# Bus.net
KiCad netlist of a schematic drawn in EAGLE
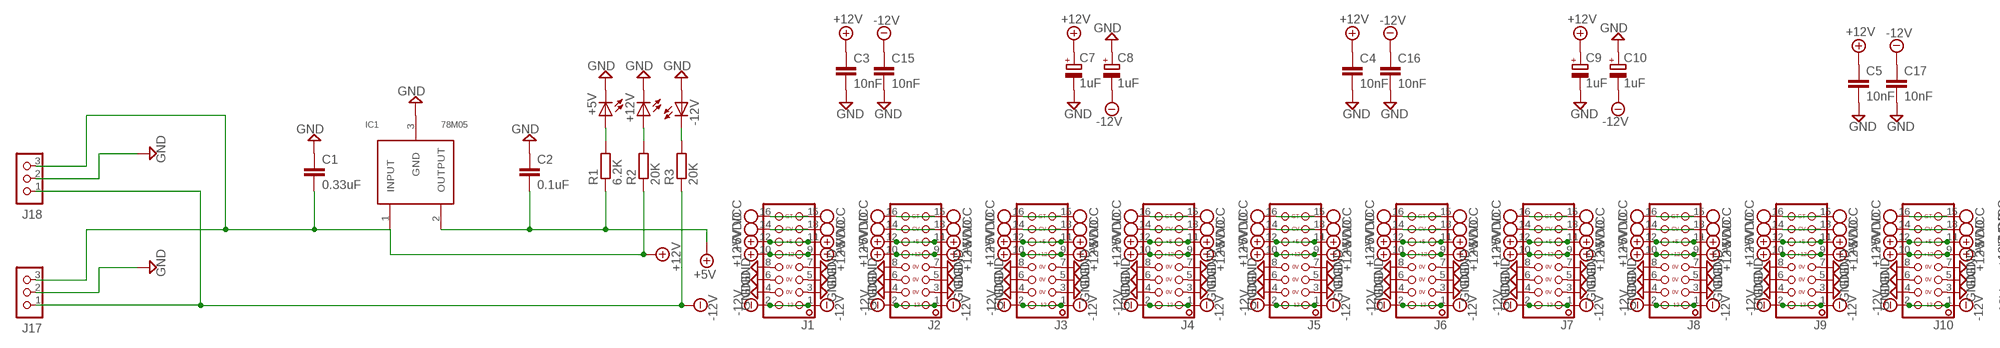
[diagram p0: schematic, sheet 1, part 1 of 2]
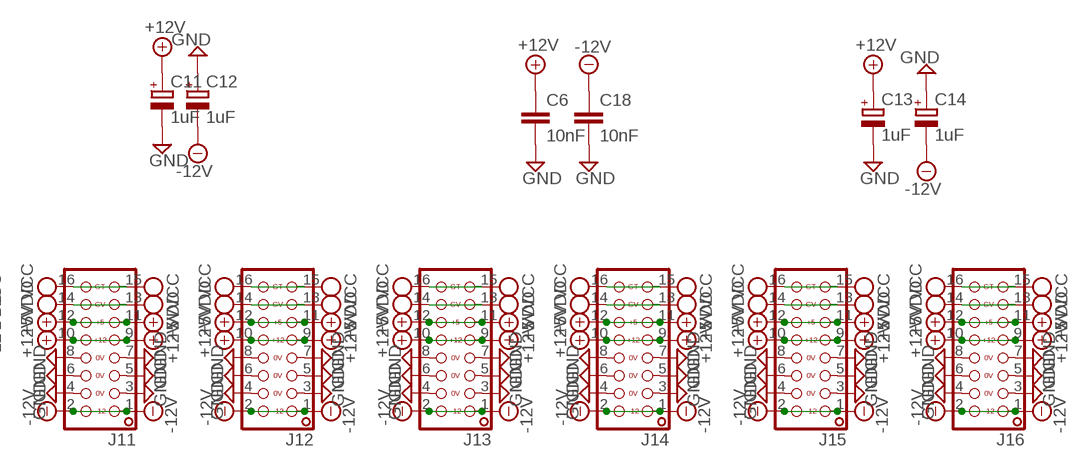
[diagram p1: schematic, sheet 1, part 2 of 2]

(export (version "E")
  (design (tool "Eeschema 10.0.6"))
  (components
    (comp (ref "+5V")
      (value "LED3MM")
      (footprint "eagle-import:LED3MM")
      (libsource (lib "eagle-import") (part "LED3MM"))
    )
    (comp (ref "+12V")
      (value "LED3MM")
      (footprint "eagle-import:LED3MM")
      (libsource (lib "eagle-import") (part "LED3MM"))
    )
    (comp (ref "-12V")
      (value "LED3MM")
      (footprint "eagle-import:LED3MM")
      (libsource (lib "eagle-import") (part "LED3MM"))
    )
    (comp (ref "C1")
      (value "0.33uF")
      (footprint "eagle-import:C1206")
      (libsource (lib "eagle-import") (part "C-EUC1206"))
    )
    (comp (ref "C2")
      (value "0.1uF")
      (footprint "eagle-import:C1206")
      (libsource (lib "eagle-import") (part "C-EUC1206"))
    )
    (comp (ref "C3")
      (value "10nF")
      (footprint "eagle-import:C1206")
      (libsource (lib "eagle-import") (part "C-EUC1206"))
    )
    (comp (ref "C4")
      (value "10nF")
      (footprint "eagle-import:C1206")
      (libsource (lib "eagle-import") (part "C-EUC1206"))
    )
    (comp (ref "C5")
      (value "10nF")
      (footprint "eagle-import:C1206")
      (libsource (lib "eagle-import") (part "C-EUC1206"))
    )
    (comp (ref "C6")
      (value "10nF")
      (footprint "eagle-import:C1206")
      (libsource (lib "eagle-import") (part "C-EUC1206"))
    )
    (comp (ref "C7")
      (value "1uF")
      (footprint "eagle-import:PANASONIC_A")
      (libsource (lib "eagle-import") (part "CPOL-EUA"))
    )
    (comp (ref "C8")
      (value "1uF")
      (footprint "eagle-import:PANASONIC_A")
      (libsource (lib "eagle-import") (part "CPOL-EUA"))
    )
    (comp (ref "C9")
      (value "1uF")
      (footprint "eagle-import:PANASONIC_A")
      (libsource (lib "eagle-import") (part "CPOL-EUA"))
    )
    (comp (ref "C10")
      (value "1uF")
      (footprint "eagle-import:PANASONIC_A")
      (libsource (lib "eagle-import") (part "CPOL-EUA"))
    )
    (comp (ref "C11")
      (value "1uF")
      (footprint "eagle-import:PANASONIC_A")
      (libsource (lib "eagle-import") (part "CPOL-EUA"))
    )
    (comp (ref "C12")
      (value "1uF")
      (footprint "eagle-import:PANASONIC_A")
      (libsource (lib "eagle-import") (part "CPOL-EUA"))
    )
    (comp (ref "C13")
      (value "1uF")
      (footprint "eagle-import:PANASONIC_A")
      (libsource (lib "eagle-import") (part "CPOL-EUA"))
    )
    (comp (ref "C14")
      (value "1uF")
      (footprint "eagle-import:PANASONIC_A")
      (libsource (lib "eagle-import") (part "CPOL-EUA"))
    )
    (comp (ref "C15")
      (value "10nF")
      (footprint "eagle-import:C1206")
      (libsource (lib "eagle-import") (part "C-EUC1206"))
    )
    (comp (ref "C16")
      (value "10nF")
      (footprint "eagle-import:C1206")
      (libsource (lib "eagle-import") (part "C-EUC1206"))
    )
    (comp (ref "C17")
      (value "10nF")
      (footprint "eagle-import:C1206")
      (libsource (lib "eagle-import") (part "C-EUC1206"))
    )
    (comp (ref "C18")
      (value "10nF")
      (footprint "eagle-import:C1206")
      (libsource (lib "eagle-import") (part "C-EUC1206"))
    )
    (comp (ref "IC1")
      (value "78M05")
      (footprint "eagle-import:TO252")
      (libsource (lib "eagle-import") (part "78MXX"))
    )
    (comp (ref "J1")
      (value "EUROPWR_2X08-SHROUD")
      (footprint "eagle-import:2X08_EUROPWR_SHROUD")
      (libsource (lib "eagle-import") (part "EUROPWR_2X08-SHROUD"))
    )
    (comp (ref "J2")
      (value "EUROPWR_2X08-SHROUD")
      (footprint "eagle-import:2X08_EUROPWR_SHROUD")
      (libsource (lib "eagle-import") (part "EUROPWR_2X08-SHROUD"))
    )
    (comp (ref "J3")
      (value "EUROPWR_2X08-SHROUD")
      (footprint "eagle-import:2X08_EUROPWR_SHROUD")
      (libsource (lib "eagle-import") (part "EUROPWR_2X08-SHROUD"))
    )
    (comp (ref "J4")
      (value "EUROPWR_2X08-SHROUD")
      (footprint "eagle-import:2X08_EUROPWR_SHROUD")
      (libsource (lib "eagle-import") (part "EUROPWR_2X08-SHROUD"))
    )
    (comp (ref "J5")
      (value "EUROPWR_2X08-SHROUD")
      (footprint "eagle-import:2X08_EUROPWR_SHROUD")
      (libsource (lib "eagle-import") (part "EUROPWR_2X08-SHROUD"))
    )
    (comp (ref "J6")
      (value "EUROPWR_2X08-SHROUD")
      (footprint "eagle-import:2X08_EUROPWR_SHROUD")
      (libsource (lib "eagle-import") (part "EUROPWR_2X08-SHROUD"))
    )
    (comp (ref "J7")
      (value "EUROPWR_2X08-SHROUD")
      (footprint "eagle-import:2X08_EUROPWR_SHROUD")
      (libsource (lib "eagle-import") (part "EUROPWR_2X08-SHROUD"))
    )
    (comp (ref "J8")
      (value "EUROPWR_2X08-SHROUD")
      (footprint "eagle-import:2X08_EUROPWR_SHROUD")
      (libsource (lib "eagle-import") (part "EUROPWR_2X08-SHROUD"))
    )
    (comp (ref "J9")
      (value "EUROPWR_2X08-SHROUD")
      (footprint "eagle-import:2X08_EUROPWR_SHROUD")
      (libsource (lib "eagle-import") (part "EUROPWR_2X08-SHROUD"))
    )
    (comp (ref "J10")
      (value "EUROPWR_2X08-SHROUD")
      (footprint "eagle-import:2X08_EUROPWR_SHROUD")
      (libsource (lib "eagle-import") (part "EUROPWR_2X08-SHROUD"))
    )
    (comp (ref "J11")
      (value "EUROPWR_2X08-SHROUD")
      (footprint "eagle-import:2X08_EUROPWR_SHROUD")
      (libsource (lib "eagle-import") (part "EUROPWR_2X08-SHROUD"))
    )
    (comp (ref "J12")
      (value "EUROPWR_2X08-SHROUD")
      (footprint "eagle-import:2X08_EUROPWR_SHROUD")
      (libsource (lib "eagle-import") (part "EUROPWR_2X08-SHROUD"))
    )
    (comp (ref "J13")
      (value "EUROPWR_2X08-SHROUD")
      (footprint "eagle-import:2X08_EUROPWR_SHROUD")
      (libsource (lib "eagle-import") (part "EUROPWR_2X08-SHROUD"))
    )
    (comp (ref "J14")
      (value "EUROPWR_2X08-SHROUD")
      (footprint "eagle-import:2X08_EUROPWR_SHROUD")
      (libsource (lib "eagle-import") (part "EUROPWR_2X08-SHROUD"))
    )
    (comp (ref "J15")
      (value "EUROPWR_2X08-SHROUD")
      (footprint "eagle-import:2X08_EUROPWR_SHROUD")
      (libsource (lib "eagle-import") (part "EUROPWR_2X08-SHROUD"))
    )
    (comp (ref "J16")
      (value "EUROPWR_2X08-SHROUD")
      (footprint "eagle-import:2X08_EUROPWR_SHROUD")
      (libsource (lib "eagle-import") (part "EUROPWR_2X08-SHROUD"))
    )
    (comp (ref "J17")
      (value "CON_TERMINAL_BLOCK_03-5MM")
      (footprint "eagle-import:TERMINAL_BLOCK_3P_5")
      (libsource (lib "eagle-import") (part "CON_TERMINAL_BLOCK_03-5MM"))
    )
    (comp (ref "J18")
      (value "CON_TERMINAL_BLOCK_03-5MM")
      (footprint "eagle-import:TERMINAL_BLOCK_3P_5")
      (libsource (lib "eagle-import") (part "CON_TERMINAL_BLOCK_03-5MM"))
    )
    (comp (ref "R1")
      (value "6.2K")
      (footprint "eagle-import:R1206")
      (libsource (lib "eagle-import") (part "R-EU_R1206"))
    )
    (comp (ref "R2")
      (value "20K")
      (footprint "eagle-import:R1206")
      (libsource (lib "eagle-import") (part "R-EU_R1206"))
    )
    (comp (ref "R3")
      (value "20K")
      (footprint "eagle-import:R1206")
      (libsource (lib "eagle-import") (part "R-EU_R1206"))
    )
  )
  (nets
    (net (code "1") (name "+5V") (class "Default")
      (node (ref "C2") (pin "2") (pinfunction "2_2") (pintype "passive"))
      (node (ref "IC1") (pin "2") (pinfunction "OUTPUT_2") (pintype "bidirectional"))
      (node (ref "J1") (pin "11") (pinfunction "11_11") (pintype "passive"))
      (node (ref "J1") (pin "12") (pinfunction "12_12") (pintype "passive"))
      (node (ref "J10") (pin "11") (pinfunction "11_11") (pintype "passive"))
      (node (ref "J10") (pin "12") (pinfunction "12_12") (pintype "passive"))
      (node (ref "J11") (pin "11") (pinfunction "11_11") (pintype "passive"))
      (node (ref "J11") (pin "12") (pinfunction "12_12") (pintype "passive"))
      (node (ref "J12") (pin "11") (pinfunction "11_11") (pintype "passive"))
      (node (ref "J12") (pin "12") (pinfunction "12_12") (pintype "passive"))
      (node (ref "J13") (pin "11") (pinfunction "11_11") (pintype "passive"))
      (node (ref "J13") (pin "12") (pinfunction "12_12") (pintype "passive"))
      (node (ref "J14") (pin "11") (pinfunction "11_11") (pintype "passive"))
      (node (ref "J14") (pin "12") (pinfunction "12_12") (pintype "passive"))
      (node (ref "J15") (pin "11") (pinfunction "11_11") (pintype "passive"))
      (node (ref "J15") (pin "12") (pinfunction "12_12") (pintype "passive"))
      (node (ref "J16") (pin "11") (pinfunction "11_11") (pintype "passive"))
      (node (ref "J16") (pin "12") (pinfunction "12_12") (pintype "passive"))
      (node (ref "J2") (pin "11") (pinfunction "11_11") (pintype "passive"))
      (node (ref "J2") (pin "12") (pinfunction "12_12") (pintype "passive"))
      (node (ref "J3") (pin "11") (pinfunction "11_11") (pintype "passive"))
      (node (ref "J3") (pin "12") (pinfunction "12_12") (pintype "passive"))
      (node (ref "J4") (pin "11") (pinfunction "11_11") (pintype "passive"))
      (node (ref "J4") (pin "12") (pinfunction "12_12") (pintype "passive"))
      (node (ref "J5") (pin "11") (pinfunction "11_11") (pintype "passive"))
      (node (ref "J5") (pin "12") (pinfunction "12_12") (pintype "passive"))
      (node (ref "J6") (pin "11") (pinfunction "11_11") (pintype "passive"))
      (node (ref "J6") (pin "12") (pinfunction "12_12") (pintype "passive"))
      (node (ref "J7") (pin "11") (pinfunction "11_11") (pintype "passive"))
      (node (ref "J7") (pin "12") (pinfunction "12_12") (pintype "passive"))
      (node (ref "J8") (pin "11") (pinfunction "11_11") (pintype "passive"))
      (node (ref "J8") (pin "12") (pinfunction "12_12") (pintype "passive"))
      (node (ref "J9") (pin "11") (pinfunction "11_11") (pintype "passive"))
      (node (ref "J9") (pin "12") (pinfunction "12_12") (pintype "passive"))
      (node (ref "R1") (pin "1") (pinfunction "1_1") (pintype "passive"))
    )
    (net (code "2") (name "+12V") (class "Default")
      (node (ref "C1") (pin "2") (pinfunction "2_2") (pintype "passive"))
      (node (ref "C11") (pin "+") (pinfunction "+_+") (pintype "passive"))
      (node (ref "C13") (pin "+") (pinfunction "+_+") (pintype "passive"))
      (node (ref "C3") (pin "1") (pinfunction "1_1") (pintype "passive"))
      (node (ref "C4") (pin "1") (pinfunction "1_1") (pintype "passive"))
      (node (ref "C5") (pin "1") (pinfunction "1_1") (pintype "passive"))
      (node (ref "C6") (pin "1") (pinfunction "1_1") (pintype "passive"))
      (node (ref "C7") (pin "+") (pinfunction "+_+") (pintype "passive"))
      (node (ref "C9") (pin "+") (pinfunction "+_+") (pintype "passive"))
      (node (ref "IC1") (pin "1") (pinfunction "INPUT_1") (pintype "bidirectional"))
      (node (ref "J1") (pin "10") (pinfunction "10_10") (pintype "passive"))
      (node (ref "J1") (pin "9") (pinfunction "9_9") (pintype "passive"))
      (node (ref "J10") (pin "10") (pinfunction "10_10") (pintype "passive"))
      (node (ref "J10") (pin "9") (pinfunction "9_9") (pintype "passive"))
      (node (ref "J11") (pin "10") (pinfunction "10_10") (pintype "passive"))
      (node (ref "J11") (pin "9") (pinfunction "9_9") (pintype "passive"))
      (node (ref "J12") (pin "10") (pinfunction "10_10") (pintype "passive"))
      (node (ref "J12") (pin "9") (pinfunction "9_9") (pintype "passive"))
      (node (ref "J13") (pin "10") (pinfunction "10_10") (pintype "passive"))
      (node (ref "J13") (pin "9") (pinfunction "9_9") (pintype "passive"))
      (node (ref "J14") (pin "10") (pinfunction "10_10") (pintype "passive"))
      (node (ref "J14") (pin "9") (pinfunction "9_9") (pintype "passive"))
      (node (ref "J15") (pin "10") (pinfunction "10_10") (pintype "passive"))
      (node (ref "J15") (pin "9") (pinfunction "9_9") (pintype "passive"))
      (node (ref "J16") (pin "10") (pinfunction "10_10") (pintype "passive"))
      (node (ref "J16") (pin "9") (pinfunction "9_9") (pintype "passive"))
      (node (ref "J17") (pin "3") (pinfunction "3_3") (pintype "bidirectional"))
      (node (ref "J18") (pin "3") (pinfunction "3_3") (pintype "bidirectional"))
      (node (ref "J2") (pin "10") (pinfunction "10_10") (pintype "passive"))
      (node (ref "J2") (pin "9") (pinfunction "9_9") (pintype "passive"))
      (node (ref "J3") (pin "10") (pinfunction "10_10") (pintype "passive"))
      (node (ref "J3") (pin "9") (pinfunction "9_9") (pintype "passive"))
      (node (ref "J4") (pin "10") (pinfunction "10_10") (pintype "passive"))
      (node (ref "J4") (pin "9") (pinfunction "9_9") (pintype "passive"))
      (node (ref "J5") (pin "10") (pinfunction "10_10") (pintype "passive"))
      (node (ref "J5") (pin "9") (pinfunction "9_9") (pintype "passive"))
      (node (ref "J6") (pin "10") (pinfunction "10_10") (pintype "passive"))
      (node (ref "J6") (pin "9") (pinfunction "9_9") (pintype "passive"))
      (node (ref "J7") (pin "10") (pinfunction "10_10") (pintype "passive"))
      (node (ref "J7") (pin "9") (pinfunction "9_9") (pintype "passive"))
      (node (ref "J8") (pin "10") (pinfunction "10_10") (pintype "passive"))
      (node (ref "J8") (pin "9") (pinfunction "9_9") (pintype "passive"))
      (node (ref "J9") (pin "10") (pinfunction "10_10") (pintype "passive"))
      (node (ref "J9") (pin "9") (pinfunction "9_9") (pintype "passive"))
      (node (ref "R2") (pin "1") (pinfunction "1_1") (pintype "passive"))
    )
    (net (code "3") (name "-12V") (class "Default")
      (node (ref "C10") (pin "-") (pinfunction "-_-") (pintype "passive"))
      (node (ref "C12") (pin "-") (pinfunction "-_-") (pintype "passive"))
      (node (ref "C14") (pin "-") (pinfunction "-_-") (pintype "passive"))
      (node (ref "C15") (pin "1") (pinfunction "1_1") (pintype "passive"))
      (node (ref "C16") (pin "1") (pinfunction "1_1") (pintype "passive"))
      (node (ref "C17") (pin "1") (pinfunction "1_1") (pintype "passive"))
      (node (ref "C18") (pin "1") (pinfunction "1_1") (pintype "passive"))
      (node (ref "C8") (pin "-") (pinfunction "-_-") (pintype "passive"))
      (node (ref "J1") (pin "1") (pinfunction "1_1") (pintype "passive"))
      (node (ref "J1") (pin "2") (pinfunction "2_2") (pintype "passive"))
      (node (ref "J10") (pin "1") (pinfunction "1_1") (pintype "passive"))
      (node (ref "J10") (pin "2") (pinfunction "2_2") (pintype "passive"))
      (node (ref "J11") (pin "1") (pinfunction "1_1") (pintype "passive"))
      (node (ref "J11") (pin "2") (pinfunction "2_2") (pintype "passive"))
      (node (ref "J12") (pin "1") (pinfunction "1_1") (pintype "passive"))
      (node (ref "J12") (pin "2") (pinfunction "2_2") (pintype "passive"))
      (node (ref "J13") (pin "1") (pinfunction "1_1") (pintype "passive"))
      (node (ref "J13") (pin "2") (pinfunction "2_2") (pintype "passive"))
      (node (ref "J14") (pin "1") (pinfunction "1_1") (pintype "passive"))
      (node (ref "J14") (pin "2") (pinfunction "2_2") (pintype "passive"))
      (node (ref "J15") (pin "1") (pinfunction "1_1") (pintype "passive"))
      (node (ref "J15") (pin "2") (pinfunction "2_2") (pintype "passive"))
      (node (ref "J16") (pin "1") (pinfunction "1_1") (pintype "passive"))
      (node (ref "J16") (pin "2") (pinfunction "2_2") (pintype "passive"))
      (node (ref "J17") (pin "1") (pinfunction "1_1") (pintype "bidirectional"))
      (node (ref "J18") (pin "1") (pinfunction "1_1") (pintype "bidirectional"))
      (node (ref "J2") (pin "1") (pinfunction "1_1") (pintype "passive"))
      (node (ref "J2") (pin "2") (pinfunction "2_2") (pintype "passive"))
      (node (ref "J3") (pin "1") (pinfunction "1_1") (pintype "passive"))
      (node (ref "J3") (pin "2") (pinfunction "2_2") (pintype "passive"))
      (node (ref "J4") (pin "1") (pinfunction "1_1") (pintype "passive"))
      (node (ref "J4") (pin "2") (pinfunction "2_2") (pintype "passive"))
      (node (ref "J5") (pin "1") (pinfunction "1_1") (pintype "passive"))
      (node (ref "J5") (pin "2") (pinfunction "2_2") (pintype "passive"))
      (node (ref "J6") (pin "1") (pinfunction "1_1") (pintype "passive"))
      (node (ref "J6") (pin "2") (pinfunction "2_2") (pintype "passive"))
      (node (ref "J7") (pin "1") (pinfunction "1_1") (pintype "passive"))
      (node (ref "J7") (pin "2") (pinfunction "2_2") (pintype "passive"))
      (node (ref "J8") (pin "1") (pinfunction "1_1") (pintype "passive"))
      (node (ref "J8") (pin "2") (pinfunction "2_2") (pintype "passive"))
      (node (ref "J9") (pin "1") (pinfunction "1_1") (pintype "passive"))
      (node (ref "J9") (pin "2") (pinfunction "2_2") (pintype "passive"))
      (node (ref "R3") (pin "1") (pinfunction "1_1") (pintype "passive"))
    )
    (net (code "4") (name "GND") (class "Default")
      (node (ref "+12V") (pin "K") (pinfunction "C_K") (pintype "passive"))
      (node (ref "+5V") (pin "K") (pinfunction "C_K") (pintype "passive"))
      (node (ref "-12V") (pin "A") (pinfunction "A_A") (pintype "passive"))
      (node (ref "C1") (pin "1") (pinfunction "1_1") (pintype "passive"))
      (node (ref "C10") (pin "+") (pinfunction "+_+") (pintype "passive"))
      (node (ref "C11") (pin "-") (pinfunction "-_-") (pintype "passive"))
      (node (ref "C12") (pin "+") (pinfunction "+_+") (pintype "passive"))
      (node (ref "C13") (pin "-") (pinfunction "-_-") (pintype "passive"))
      (node (ref "C14") (pin "+") (pinfunction "+_+") (pintype "passive"))
      (node (ref "C15") (pin "2") (pinfunction "2_2") (pintype "passive"))
      (node (ref "C16") (pin "2") (pinfunction "2_2") (pintype "passive"))
      (node (ref "C17") (pin "2") (pinfunction "2_2") (pintype "passive"))
      (node (ref "C18") (pin "2") (pinfunction "2_2") (pintype "passive"))
      (node (ref "C2") (pin "1") (pinfunction "1_1") (pintype "passive"))
      (node (ref "C3") (pin "2") (pinfunction "2_2") (pintype "passive"))
      (node (ref "C4") (pin "2") (pinfunction "2_2") (pintype "passive"))
      (node (ref "C5") (pin "2") (pinfunction "2_2") (pintype "passive"))
      (node (ref "C6") (pin "2") (pinfunction "2_2") (pintype "passive"))
      (node (ref "C7") (pin "-") (pinfunction "-_-") (pintype "passive"))
      (node (ref "C8") (pin "+") (pinfunction "+_+") (pintype "passive"))
      (node (ref "C9") (pin "-") (pinfunction "-_-") (pintype "passive"))
      (node (ref "IC1") (pin "3") (pinfunction "GND_3") (pintype "bidirectional"))
      (node (ref "J1") (pin "3") (pinfunction "3_3") (pintype "passive"))
      (node (ref "J1") (pin "4") (pinfunction "4_4") (pintype "passive"))
      (node (ref "J1") (pin "5") (pinfunction "5_5") (pintype "passive"))
      (node (ref "J1") (pin "6") (pinfunction "6_6") (pintype "passive"))
      (node (ref "J1") (pin "7") (pinfunction "7_7") (pintype "passive"))
      (node (ref "J1") (pin "8") (pinfunction "8_8") (pintype "passive"))
      (node (ref "J10") (pin "3") (pinfunction "3_3") (pintype "passive"))
      (node (ref "J10") (pin "4") (pinfunction "4_4") (pintype "passive"))
      (node (ref "J10") (pin "5") (pinfunction "5_5") (pintype "passive"))
      (node (ref "J10") (pin "6") (pinfunction "6_6") (pintype "passive"))
      (node (ref "J10") (pin "7") (pinfunction "7_7") (pintype "passive"))
      (node (ref "J10") (pin "8") (pinfunction "8_8") (pintype "passive"))
      (node (ref "J11") (pin "3") (pinfunction "3_3") (pintype "passive"))
      (node (ref "J11") (pin "4") (pinfunction "4_4") (pintype "passive"))
      (node (ref "J11") (pin "5") (pinfunction "5_5") (pintype "passive"))
      (node (ref "J11") (pin "6") (pinfunction "6_6") (pintype "passive"))
      (node (ref "J11") (pin "7") (pinfunction "7_7") (pintype "passive"))
      (node (ref "J11") (pin "8") (pinfunction "8_8") (pintype "passive"))
      (node (ref "J12") (pin "3") (pinfunction "3_3") (pintype "passive"))
      (node (ref "J12") (pin "4") (pinfunction "4_4") (pintype "passive"))
      (node (ref "J12") (pin "5") (pinfunction "5_5") (pintype "passive"))
      (node (ref "J12") (pin "6") (pinfunction "6_6") (pintype "passive"))
      (node (ref "J12") (pin "7") (pinfunction "7_7") (pintype "passive"))
      (node (ref "J12") (pin "8") (pinfunction "8_8") (pintype "passive"))
      (node (ref "J13") (pin "3") (pinfunction "3_3") (pintype "passive"))
      (node (ref "J13") (pin "4") (pinfunction "4_4") (pintype "passive"))
      (node (ref "J13") (pin "5") (pinfunction "5_5") (pintype "passive"))
      (node (ref "J13") (pin "6") (pinfunction "6_6") (pintype "passive"))
      (node (ref "J13") (pin "7") (pinfunction "7_7") (pintype "passive"))
      (node (ref "J13") (pin "8") (pinfunction "8_8") (pintype "passive"))
      (node (ref "J14") (pin "3") (pinfunction "3_3") (pintype "passive"))
      (node (ref "J14") (pin "4") (pinfunction "4_4") (pintype "passive"))
      (node (ref "J14") (pin "5") (pinfunction "5_5") (pintype "passive"))
      (node (ref "J14") (pin "6") (pinfunction "6_6") (pintype "passive"))
      (node (ref "J14") (pin "7") (pinfunction "7_7") (pintype "passive"))
      (node (ref "J14") (pin "8") (pinfunction "8_8") (pintype "passive"))
      (node (ref "J15") (pin "3") (pinfunction "3_3") (pintype "passive"))
      (node (ref "J15") (pin "4") (pinfunction "4_4") (pintype "passive"))
      (node (ref "J15") (pin "5") (pinfunction "5_5") (pintype "passive"))
      (node (ref "J15") (pin "6") (pinfunction "6_6") (pintype "passive"))
      (node (ref "J15") (pin "7") (pinfunction "7_7") (pintype "passive"))
      (node (ref "J15") (pin "8") (pinfunction "8_8") (pintype "passive"))
      (node (ref "J16") (pin "3") (pinfunction "3_3") (pintype "passive"))
      (node (ref "J16") (pin "4") (pinfunction "4_4") (pintype "passive"))
      (node (ref "J16") (pin "5") (pinfunction "5_5") (pintype "passive"))
      (node (ref "J16") (pin "6") (pinfunction "6_6") (pintype "passive"))
      (node (ref "J16") (pin "7") (pinfunction "7_7") (pintype "passive"))
      (node (ref "J16") (pin "8") (pinfunction "8_8") (pintype "passive"))
      (node (ref "J17") (pin "2") (pinfunction "2_2") (pintype "bidirectional"))
      (node (ref "J18") (pin "2") (pinfunction "2_2") (pintype "bidirectional"))
      (node (ref "J2") (pin "3") (pinfunction "3_3") (pintype "passive"))
      (node (ref "J2") (pin "4") (pinfunction "4_4") (pintype "passive"))
      (node (ref "J2") (pin "5") (pinfunction "5_5") (pintype "passive"))
      (node (ref "J2") (pin "6") (pinfunction "6_6") (pintype "passive"))
      (node (ref "J2") (pin "7") (pinfunction "7_7") (pintype "passive"))
      (node (ref "J2") (pin "8") (pinfunction "8_8") (pintype "passive"))
      (node (ref "J3") (pin "3") (pinfunction "3_3") (pintype "passive"))
      (node (ref "J3") (pin "4") (pinfunction "4_4") (pintype "passive"))
      (node (ref "J3") (pin "5") (pinfunction "5_5") (pintype "passive"))
      (node (ref "J3") (pin "6") (pinfunction "6_6") (pintype "passive"))
      (node (ref "J3") (pin "7") (pinfunction "7_7") (pintype "passive"))
      (node (ref "J3") (pin "8") (pinfunction "8_8") (pintype "passive"))
      (node (ref "J4") (pin "3") (pinfunction "3_3") (pintype "passive"))
      (node (ref "J4") (pin "4") (pinfunction "4_4") (pintype "passive"))
      (node (ref "J4") (pin "5") (pinfunction "5_5") (pintype "passive"))
      (node (ref "J4") (pin "6") (pinfunction "6_6") (pintype "passive"))
      (node (ref "J4") (pin "7") (pinfunction "7_7") (pintype "passive"))
      (node (ref "J4") (pin "8") (pinfunction "8_8") (pintype "passive"))
      (node (ref "J5") (pin "3") (pinfunction "3_3") (pintype "passive"))
      (node (ref "J5") (pin "4") (pinfunction "4_4") (pintype "passive"))
      (node (ref "J5") (pin "5") (pinfunction "5_5") (pintype "passive"))
      (node (ref "J5") (pin "6") (pinfunction "6_6") (pintype "passive"))
      (node (ref "J5") (pin "7") (pinfunction "7_7") (pintype "passive"))
      (node (ref "J5") (pin "8") (pinfunction "8_8") (pintype "passive"))
      (node (ref "J6") (pin "3") (pinfunction "3_3") (pintype "passive"))
      (node (ref "J6") (pin "4") (pinfunction "4_4") (pintype "passive"))
      (node (ref "J6") (pin "5") (pinfunction "5_5") (pintype "passive"))
      (node (ref "J6") (pin "6") (pinfunction "6_6") (pintype "passive"))
      (node (ref "J6") (pin "7") (pinfunction "7_7") (pintype "passive"))
      (node (ref "J6") (pin "8") (pinfunction "8_8") (pintype "passive"))
      (node (ref "J7") (pin "3") (pinfunction "3_3") (pintype "passive"))
      (node (ref "J7") (pin "4") (pinfunction "4_4") (pintype "passive"))
      (node (ref "J7") (pin "5") (pinfunction "5_5") (pintype "passive"))
      (node (ref "J7") (pin "6") (pinfunction "6_6") (pintype "passive"))
      (node (ref "J7") (pin "7") (pinfunction "7_7") (pintype "passive"))
      (node (ref "J7") (pin "8") (pinfunction "8_8") (pintype "passive"))
      (node (ref "J8") (pin "3") (pinfunction "3_3") (pintype "passive"))
      (node (ref "J8") (pin "4") (pinfunction "4_4") (pintype "passive"))
      (node (ref "J8") (pin "5") (pinfunction "5_5") (pintype "passive"))
      (node (ref "J8") (pin "6") (pinfunction "6_6") (pintype "passive"))
      (node (ref "J8") (pin "7") (pinfunction "7_7") (pintype "passive"))
      (node (ref "J8") (pin "8") (pinfunction "8_8") (pintype "passive"))
      (node (ref "J9") (pin "3") (pinfunction "3_3") (pintype "passive"))
      (node (ref "J9") (pin "4") (pinfunction "4_4") (pintype "passive"))
      (node (ref "J9") (pin "5") (pinfunction "5_5") (pintype "passive"))
      (node (ref "J9") (pin "6") (pinfunction "6_6") (pintype "passive"))
      (node (ref "J9") (pin "7") (pinfunction "7_7") (pintype "passive"))
      (node (ref "J9") (pin "8") (pinfunction "8_8") (pintype "passive"))
    )
    (net (code "5") (name "Net-(+5V-PadA)") (class "Default")
      (node (ref "+5V") (pin "A") (pinfunction "A_A") (pintype "passive"))
      (node (ref "R1") (pin "2") (pinfunction "2_2") (pintype "passive"))
    )
    (net (code "6") (name "Net-(+12V-PadA)") (class "Default")
      (node (ref "+12V") (pin "A") (pinfunction "A_A") (pintype "passive"))
      (node (ref "R2") (pin "2") (pinfunction "2_2") (pintype "passive"))
    )
    (net (code "7") (name "Net-(-12V-C)") (class "Default")
      (node (ref "-12V") (pin "K") (pinfunction "C_K") (pintype "passive"))
      (node (ref "R3") (pin "2") (pinfunction "2_2") (pintype "passive"))
    )
    (net (code "8") (name "VCC") (class "Default")
      (node (ref "J1") (pin "15") (pinfunction "15_15") (pintype "passive"))
      (node (ref "J1") (pin "16") (pinfunction "16_16") (pintype "passive"))
      (node (ref "J10") (pin "15") (pinfunction "15_15") (pintype "passive"))
      (node (ref "J10") (pin "16") (pinfunction "16_16") (pintype "passive"))
      (node (ref "J11") (pin "15") (pinfunction "15_15") (pintype "passive"))
      (node (ref "J11") (pin "16") (pinfunction "16_16") (pintype "passive"))
      (node (ref "J12") (pin "15") (pinfunction "15_15") (pintype "passive"))
      (node (ref "J12") (pin "16") (pinfunction "16_16") (pintype "passive"))
      (node (ref "J13") (pin "15") (pinfunction "15_15") (pintype "passive"))
      (node (ref "J13") (pin "16") (pinfunction "16_16") (pintype "passive"))
      (node (ref "J14") (pin "15") (pinfunction "15_15") (pintype "passive"))
      (node (ref "J14") (pin "16") (pinfunction "16_16") (pintype "passive"))
      (node (ref "J15") (pin "15") (pinfunction "15_15") (pintype "passive"))
      (node (ref "J15") (pin "16") (pinfunction "16_16") (pintype "passive"))
      (node (ref "J16") (pin "15") (pinfunction "15_15") (pintype "passive"))
      (node (ref "J16") (pin "16") (pinfunction "16_16") (pintype "passive"))
      (node (ref "J2") (pin "15") (pinfunction "15_15") (pintype "passive"))
      (node (ref "J2") (pin "16") (pinfunction "16_16") (pintype "passive"))
      (node (ref "J3") (pin "15") (pinfunction "15_15") (pintype "passive"))
      (node (ref "J3") (pin "16") (pinfunction "16_16") (pintype "passive"))
      (node (ref "J4") (pin "15") (pinfunction "15_15") (pintype "passive"))
      (node (ref "J4") (pin "16") (pinfunction "16_16") (pintype "passive"))
      (node (ref "J5") (pin "15") (pinfunction "15_15") (pintype "passive"))
      (node (ref "J5") (pin "16") (pinfunction "16_16") (pintype "passive"))
      (node (ref "J6") (pin "15") (pinfunction "15_15") (pintype "passive"))
      (node (ref "J6") (pin "16") (pinfunction "16_16") (pintype "passive"))
      (node (ref "J7") (pin "15") (pinfunction "15_15") (pintype "passive"))
      (node (ref "J7") (pin "16") (pinfunction "16_16") (pintype "passive"))
      (node (ref "J8") (pin "15") (pinfunction "15_15") (pintype "passive"))
      (node (ref "J8") (pin "16") (pinfunction "16_16") (pintype "passive"))
      (node (ref "J9") (pin "15") (pinfunction "15_15") (pintype "passive"))
      (node (ref "J9") (pin "16") (pinfunction "16_16") (pintype "passive"))
    )
    (net (code "9") (name "VDD") (class "Default")
      (node (ref "J1") (pin "13") (pinfunction "13_13") (pintype "passive"))
      (node (ref "J1") (pin "14") (pinfunction "14_14") (pintype "passive"))
      (node (ref "J10") (pin "13") (pinfunction "13_13") (pintype "passive"))
      (node (ref "J10") (pin "14") (pinfunction "14_14") (pintype "passive"))
      (node (ref "J11") (pin "13") (pinfunction "13_13") (pintype "passive"))
      (node (ref "J11") (pin "14") (pinfunction "14_14") (pintype "passive"))
      (node (ref "J12") (pin "13") (pinfunction "13_13") (pintype "passive"))
      (node (ref "J12") (pin "14") (pinfunction "14_14") (pintype "passive"))
      (node (ref "J13") (pin "13") (pinfunction "13_13") (pintype "passive"))
      (node (ref "J13") (pin "14") (pinfunction "14_14") (pintype "passive"))
      (node (ref "J14") (pin "13") (pinfunction "13_13") (pintype "passive"))
      (node (ref "J14") (pin "14") (pinfunction "14_14") (pintype "passive"))
      (node (ref "J15") (pin "13") (pinfunction "13_13") (pintype "passive"))
      (node (ref "J15") (pin "14") (pinfunction "14_14") (pintype "passive"))
      (node (ref "J16") (pin "13") (pinfunction "13_13") (pintype "passive"))
      (node (ref "J16") (pin "14") (pinfunction "14_14") (pintype "passive"))
      (node (ref "J2") (pin "13") (pinfunction "13_13") (pintype "passive"))
      (node (ref "J2") (pin "14") (pinfunction "14_14") (pintype "passive"))
      (node (ref "J3") (pin "13") (pinfunction "13_13") (pintype "passive"))
      (node (ref "J3") (pin "14") (pinfunction "14_14") (pintype "passive"))
      (node (ref "J4") (pin "13") (pinfunction "13_13") (pintype "passive"))
      (node (ref "J4") (pin "14") (pinfunction "14_14") (pintype "passive"))
      (node (ref "J5") (pin "13") (pinfunction "13_13") (pintype "passive"))
      (node (ref "J5") (pin "14") (pinfunction "14_14") (pintype "passive"))
      (node (ref "J6") (pin "13") (pinfunction "13_13") (pintype "passive"))
      (node (ref "J6") (pin "14") (pinfunction "14_14") (pintype "passive"))
      (node (ref "J7") (pin "13") (pinfunction "13_13") (pintype "passive"))
      (node (ref "J7") (pin "14") (pinfunction "14_14") (pintype "passive"))
      (node (ref "J8") (pin "13") (pinfunction "13_13") (pintype "passive"))
      (node (ref "J8") (pin "14") (pinfunction "14_14") (pintype "passive"))
      (node (ref "J9") (pin "13") (pinfunction "13_13") (pintype "passive"))
      (node (ref "J9") (pin "14") (pinfunction "14_14") (pintype "passive"))
    )
  )
)
